# stm32pcb.net
KiCad netlist of a schematic drawn in Altium Designer
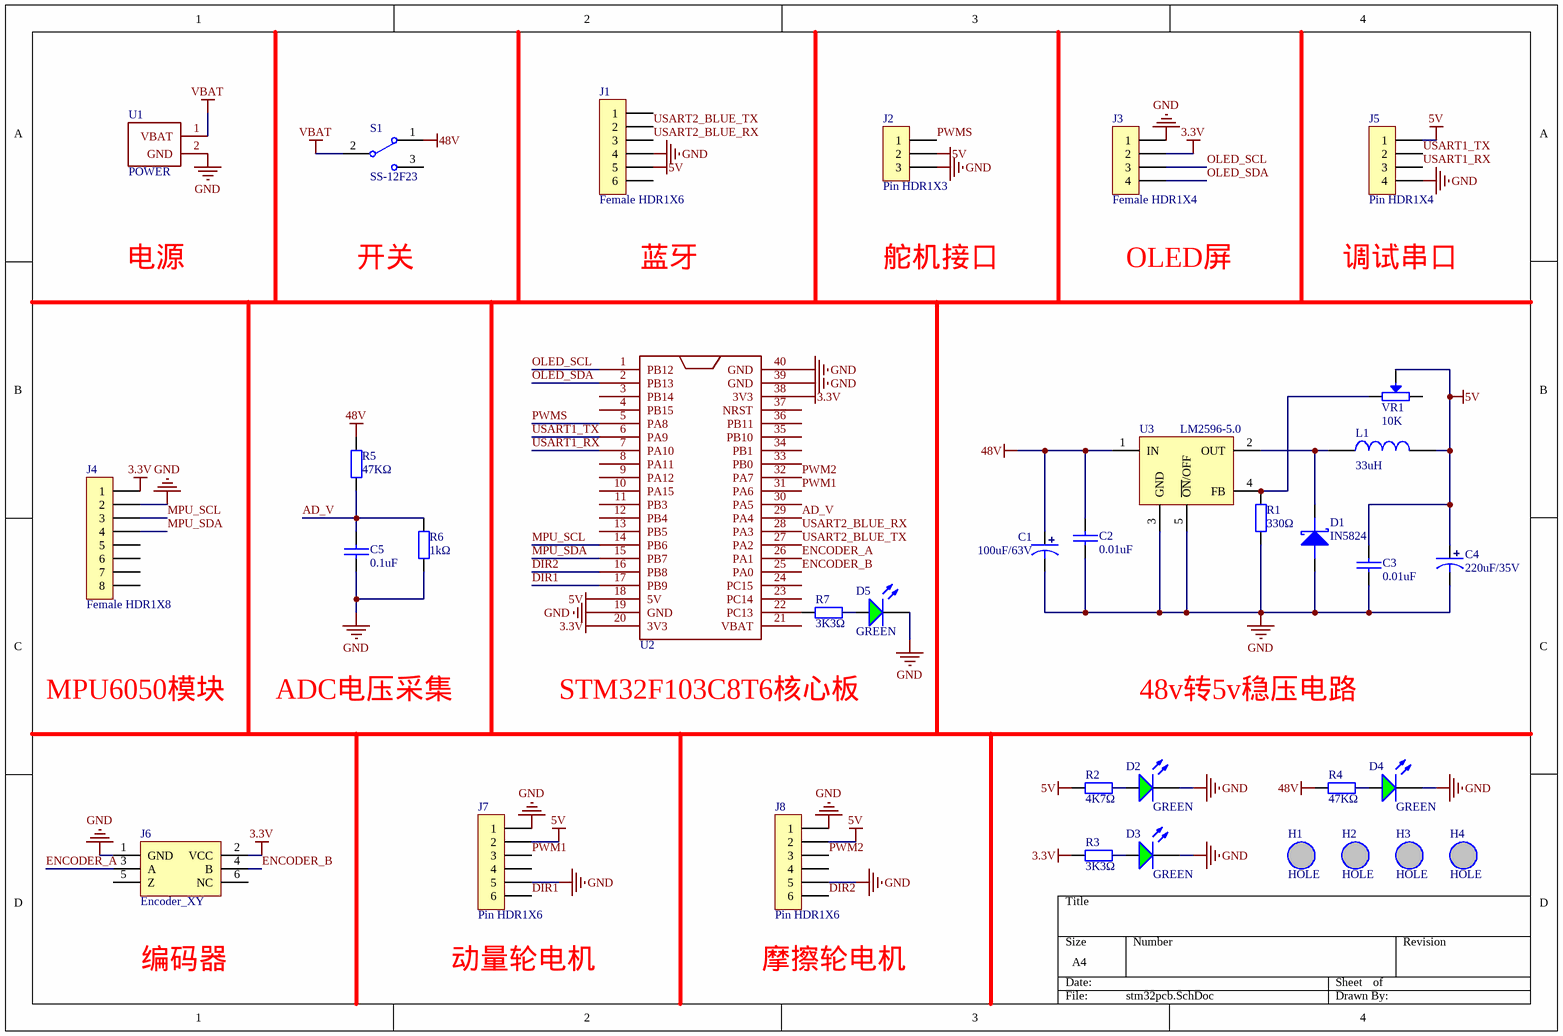
[diagram p0: stm32pcb.SchDoc]

(export (version "E")
  (design (tool "Eeschema 10.0.6"))
  (components
    (comp (ref "C1")
      (value "100uF/63V")
      (footprint "SMD-EC8X8X10")
      (description "贴片电解电容")
      (libsource (lib "self_schlib v1.8.6") (part "SMD_ECAP"))
    )
    (comp (ref "C2")
      (value "0.01uF")
      (footprint "0603C")
      (description "无极性电容")
      (libsource (lib "self_schlib v1.8.6") (part "CAP_1"))
    )
    (comp (ref "C3")
      (value "0.01uF")
      (footprint "0603C")
      (description "无极性电容")
      (libsource (lib "self_schlib v1.8.6") (part "CAP_1"))
    )
    (comp (ref "C4")
      (value "220uF/35V")
      (footprint "SMD-EC8X8X10")
      (description "贴片电解电容")
      (libsource (lib "self_schlib v1.8.6") (part "SMD_ECAP"))
    )
    (comp (ref "C5")
      (value "0.1uF")
      (footprint "0603C")
      (description "无极性电容")
      (libsource (lib "self_schlib v1.8.6") (part "CAP_1"))
    )
    (comp (ref "D1")
      (value "IN5824")
      (footprint "SMA/DO-214AC")
      (description "肖特基二极管")
      (libsource (lib "二极管") (part "DIODE SCHOTTKY"))
    )
    (comp (ref "D2")
      (value "GREEN")
      (footprint "0805_LED_S1")
      (description "发光二极管")
      (libsource (lib "Miscellaneous Devices Legend") (part "0805 翠绿"))
    )
    (comp (ref "D3")
      (value "GREEN")
      (footprint "0805_LED_S1")
      (description "发光二极管")
      (libsource (lib "Miscellaneous Devices Legend") (part "0805 翠绿"))
    )
    (comp (ref "D4")
      (value "GREEN")
      (footprint "0805_LED_S1")
      (description "发光二极管")
      (libsource (lib "Miscellaneous Devices Legend") (part "0805 翠绿"))
    )
    (comp (ref "D5")
      (value "GREEN")
      (footprint "0805_LED_S1")
      (description "发光二极管")
      (libsource (lib "Miscellaneous Devices Legend") (part "0805 翠绿"))
    )
    (comp (ref "H1")
      (value "HOLE")
      (footprint "LQ_SCROW3&5MM")
      (description "固定孔")
      (libsource (lib "test001") (part "HOLE"))
    )
    (comp (ref "H2")
      (value "HOLE")
      (footprint "LQ_SCROW3&5MM")
      (description "固定孔")
      (libsource (lib "test001") (part "HOLE"))
    )
    (comp (ref "H3")
      (value "HOLE")
      (footprint "LQ_SCROW3&5MM")
      (description "固定孔")
      (libsource (lib "test001") (part "HOLE"))
    )
    (comp (ref "H4")
      (value "HOLE")
      (footprint "LQ_SCROW3&5MM")
      (description "固定孔")
      (libsource (lib "test001") (part "HOLE"))
    )
    (comp (ref "J1")
      (value "Female HDR1X6")
      (footprint "Fe-HDR1X6/2.54-S")
      (libsource (lib "self_schlib v1.8.6") (part "Female HDR1X6"))
    )
    (comp (ref "J2")
      (value "Pin HDR1X3")
      (footprint "Pin HDR1X3/2.54mm-W")
      (libsource (lib "self_schlib v1.8.6") (part "Pin HDR1X3"))
    )
    (comp (ref "J3")
      (value "Female HDR1X4")
      (footprint "Fe-HDR1X4/2.54-S")
      (libsource (lib "self_schlib v1.8.6") (part "Female HDR1X4"))
    )
    (comp (ref "J4")
      (value "Female HDR1X8")
      (footprint "Fe-HDR1X8/2.54-S")
      (libsource (lib "self_schlib v1.8.6") (part "Female HDR1X8"))
    )
    (comp (ref "J5")
      (value "Pin HDR1X4")
      (footprint "Pin HDR1X4/2.54mm-W")
      (libsource (lib "self_schlib v1.8.6") (part "Pin HDR1X4"))
    )
    (comp (ref "J6")
      (value "Encoder_XY")
      (footprint "Pin HDR2X3/2.54mm-S")
      (description "正交编码器")
      (libsource (lib "self_schlib v1.8.6") (part "Encoder_XY"))
    )
    (comp (ref "J7")
      (value "Pin HDR1X6")
      (footprint "Pin HDR1X6/2.54mm-W")
      (libsource (lib "self_schlib v1.8.6") (part "Pin HDR1X6"))
    )
    (comp (ref "J8")
      (value "Pin HDR1X6")
      (footprint "Pin HDR1X6/2.54mm-W")
      (libsource (lib "self_schlib v1.8.6") (part "Pin HDR1X6"))
    )
    (comp (ref "L1")
      (value "33uH")
      (footprint "CD75")
      (description "INDUCTOR")
      (libsource (lib "电感") (part "INDUCTOR"))
    )
    (comp (ref "R1")
      (value "330Ω")
      (footprint "0603_R")
      (description "贴片电阻")
      (libsource (lib "") (part "0603 330Ω (3300) 1%_1"))
    )
    (comp (ref "R2")
      (value "4K7Ω")
      (footprint "0603_R")
      (description "贴片电阻")
      (libsource (lib "Miscellaneous Devices Legend") (part "0603 330Ω (3300) 1%"))
    )
    (comp (ref "R3")
      (value "3K3Ω")
      (footprint "0603_R")
      (description "贴片电阻")
      (libsource (lib "Miscellaneous Devices Legend") (part "0603 330Ω (3300) 1%"))
    )
    (comp (ref "R4")
      (value "47KΩ")
      (footprint "0603_R")
      (description "贴片电阻")
      (libsource (lib "Miscellaneous Devices Legend") (part "0603 330Ω (3300) 1%"))
    )
    (comp (ref "R5")
      (value "47KΩ")
      (footprint "0603_R")
      (description "贴片电阻")
      (libsource (lib "") (part "0603 330Ω (3300) 1%_1"))
    )
    (comp (ref "R6")
      (value "1kΩ")
      (footprint "0603_R")
      (description "贴片电阻")
      (libsource (lib "") (part "0603 330Ω (3300) 1%_1"))
    )
    (comp (ref "R7")
      (value "3K3Ω")
      (footprint "0603_R")
      (description "贴片电阻")
      (libsource (lib "Miscellaneous Devices Legend") (part "0603 330Ω (3300) 1%"))
    )
    (comp (ref "S1")
      (value "SS-12F23")
      (footprint "SS-12F23")
      (libsource (lib "self_schlib v1.8.6") (part "SS-12F23"))
    )
    (comp (ref "U1")
      (value "POWER")
      (footprint "KF301-5.0-2P")
      (libsource (lib "self_schlib v1.8.6") (part "电源焊点"))
    )
    (comp (ref "U2")
      (value "STM32F103C8T6 MODULE")
      (footprint "STM32F103C8T6 MODULE")
      (libsource (lib "self_schlib v1.8.6") (part "STM32F103C8T6 MODULE"))
    )
    (comp (ref "U3")
      (value "LM2596-5.0")
      (footprint "TO263-5A")
      (description "DC降压芯片")
      (libsource (lib "self_schlib v1.8.6") (part "LM2596-5.0"))
    )
    (comp (ref "VR1") (value "10K") (footprint "3296W") (libsource (lib "self_schlib v1.8.6") (part "RESVR")))
  )
  (nets
    (net (code "1") (name "/AD_V") (class "Default")
      (node (ref "C5") (pin "2") (pinfunction "2_2") (pintype "passive"))
      (node (ref "R5") (pin "2") (pinfunction "2_2") (pintype "passive"))
      (node (ref "R6") (pin "1") (pinfunction "1_1") (pintype "passive"))
      (node (ref "U2") (pin "29") (pinfunction "PA4_29") (pintype "passive"))
    )
    (net (code "2") (name "/DIR1") (class "Default")
      (node (ref "J7") (pin "6") (pinfunction "6_6") (pintype "passive"))
      (node (ref "U2") (pin "17") (pinfunction "PB9_17") (pintype "passive"))
    )
    (net (code "3") (name "/DIR2") (class "Default")
      (node (ref "J8") (pin "6") (pinfunction "6_6") (pintype "passive"))
      (node (ref "U2") (pin "16") (pinfunction "PB8_16") (pintype "passive"))
    )
    (net (code "4") (name "/ENCODER_A") (class "Default")
      (node (ref "J6") (pin "3") (pinfunction "A_3") (pintype "passive"))
      (node (ref "U2") (pin "26") (pinfunction "PA1_26") (pintype "passive"))
    )
    (net (code "5") (name "/ENCODER_B") (class "Default")
      (node (ref "J6") (pin "4") (pinfunction "B_4") (pintype "passive"))
      (node (ref "U2") (pin "25") (pinfunction "PA0_25") (pintype "passive"))
    )
    (net (code "6") (name "/MPU_SCL") (class "Default")
      (node (ref "J4") (pin "3") (pinfunction "3_3") (pintype "passive"))
      (node (ref "U2") (pin "14") (pinfunction "PB6_14") (pintype "passive"))
    )
    (net (code "7") (name "/MPU_SDA") (class "Default")
      (node (ref "J4") (pin "4") (pinfunction "4_4") (pintype "passive"))
      (node (ref "U2") (pin "15") (pinfunction "PB7_15") (pintype "passive"))
    )
    (net (code "8") (name "/OLED_SCL") (class "Default")
      (node (ref "J3") (pin "3") (pinfunction "3_3") (pintype "passive"))
      (node (ref "U2") (pin "1") (pinfunction "PB12_1") (pintype "passive"))
    )
    (net (code "9") (name "/OLED_SDA") (class "Default")
      (node (ref "J3") (pin "4") (pinfunction "4_4") (pintype "passive"))
      (node (ref "U2") (pin "2") (pinfunction "PB13_2") (pintype "passive"))
    )
    (net (code "10") (name "/PWM1") (class "Default")
      (node (ref "J7") (pin "3") (pinfunction "3_3") (pintype "passive"))
      (node (ref "U2") (pin "31") (pinfunction "PA6_31") (pintype "passive"))
    )
    (net (code "11") (name "/PWM2") (class "Default")
      (node (ref "J8") (pin "3") (pinfunction "3_3") (pintype "passive"))
      (node (ref "U2") (pin "32") (pinfunction "PA7_32") (pintype "passive"))
    )
    (net (code "12") (name "/PWMS") (class "Default")
      (node (ref "J2") (pin "1") (pinfunction "1_1") (pintype "passive"))
      (node (ref "U2") (pin "5") (pinfunction "PA8_5") (pintype "passive"))
    )
    (net (code "13") (name "/USART1_RX") (class "Default")
      (node (ref "J5") (pin "3") (pinfunction "3_3") (pintype "passive"))
      (node (ref "U2") (pin "7") (pinfunction "PA10_7") (pintype "passive"))
    )
    (net (code "14") (name "/USART1_TX") (class "Default")
      (node (ref "J5") (pin "2") (pinfunction "2_2") (pintype "passive"))
      (node (ref "U2") (pin "6") (pinfunction "PA9_6") (pintype "passive"))
    )
    (net (code "15") (name "/USART2_BLUE_RX") (class "Default")
      (node (ref "J1") (pin "3") (pinfunction "3_3") (pintype "passive"))
      (node (ref "U2") (pin "28") (pinfunction "PA3_28") (pintype "passive"))
    )
    (net (code "16") (name "/USART2_BLUE_TX") (class "Default")
      (node (ref "J1") (pin "2") (pinfunction "2_2") (pintype "passive"))
      (node (ref "U2") (pin "27") (pinfunction "PA2_27") (pintype "passive"))
    )
    (net (code "17") (name "3.3V") (class "Default")
      (node (ref "J3") (pin "2") (pinfunction "2_2") (pintype "passive"))
      (node (ref "J4") (pin "1") (pinfunction "1_1") (pintype "passive"))
      (node (ref "J6") (pin "2") (pinfunction "VCC_2") (pintype "passive"))
      (node (ref "R3") (pin "1") (pinfunction "1_1") (pintype "passive"))
      (node (ref "U2") (pin "20") (pinfunction "3V3_20") (pintype "passive"))
      (node (ref "U2") (pin "38") (pinfunction "3V3_38") (pintype "passive"))
    )
    (net (code "18") (name "5V") (class "Default")
      (node (ref "C3") (pin "2") (pinfunction "2_2") (pintype "passive"))
      (node (ref "C4") (pin "1") (pinfunction "1_1") (pintype "passive"))
      (node (ref "J1") (pin "5") (pinfunction "5_5") (pintype "passive"))
      (node (ref "J2") (pin "2") (pinfunction "2_2") (pintype "passive"))
      (node (ref "J5") (pin "1") (pinfunction "1_1") (pintype "passive"))
      (node (ref "J7") (pin "2") (pinfunction "2_2") (pintype "passive"))
      (node (ref "J8") (pin "2") (pinfunction "2_2") (pintype "passive"))
      (node (ref "L1") (pin "2") (pinfunction "2_2") (pintype "passive"))
      (node (ref "R2") (pin "1") (pinfunction "1_1") (pintype "passive"))
      (node (ref "U2") (pin "18") (pinfunction "5V_18") (pintype "passive"))
      (node (ref "VR1") (pin "2") (pinfunction "2_2") (pintype "passive"))
    )
    (net (code "19") (name "48V") (class "Default")
      (node (ref "C1") (pin "1") (pinfunction "1_1") (pintype "passive"))
      (node (ref "C2") (pin "2") (pinfunction "2_2") (pintype "passive"))
      (node (ref "R4") (pin "1") (pinfunction "1_1") (pintype "passive"))
      (node (ref "R5") (pin "1") (pinfunction "1_1") (pintype "passive"))
      (node (ref "S1") (pin "1") (pinfunction "1_1") (pintype "passive"))
      (node (ref "U3") (pin "1") (pinfunction "IN_1") (pintype "power_in"))
    )
    (net (code "20") (name "GND") (class "Default")
      (node (ref "C1") (pin "2") (pinfunction "2_2") (pintype "passive"))
      (node (ref "C2") (pin "1") (pinfunction "1_1") (pintype "passive"))
      (node (ref "C3") (pin "1") (pinfunction "1_1") (pintype "passive"))
      (node (ref "C4") (pin "2") (pinfunction "2_2") (pintype "passive"))
      (node (ref "C5") (pin "1") (pinfunction "1_1") (pintype "passive"))
      (node (ref "D1") (pin "A") (pinfunction "A_A") (pintype "passive"))
      (node (ref "D2") (pin "K") (pinfunction "K_K") (pintype "passive"))
      (node (ref "D3") (pin "K") (pinfunction "K_K") (pintype "passive"))
      (node (ref "D4") (pin "K") (pinfunction "K_K") (pintype "passive"))
      (node (ref "D5") (pin "K") (pinfunction "K_K") (pintype "passive"))
      (node (ref "J1") (pin "4") (pinfunction "4_4") (pintype "passive"))
      (node (ref "J2") (pin "3") (pinfunction "3_3") (pintype "passive"))
      (node (ref "J3") (pin "1") (pinfunction "1_1") (pintype "passive"))
      (node (ref "J4") (pin "2") (pinfunction "2_2") (pintype "passive"))
      (node (ref "J5") (pin "4") (pinfunction "4_4") (pintype "passive"))
      (node (ref "J6") (pin "1") (pinfunction "GND_1") (pintype "passive"))
      (node (ref "J7") (pin "1") (pinfunction "1_1") (pintype "passive"))
      (node (ref "J7") (pin "5") (pinfunction "5_5") (pintype "passive"))
      (node (ref "J8") (pin "1") (pinfunction "1_1") (pintype "passive"))
      (node (ref "J8") (pin "5") (pinfunction "5_5") (pintype "passive"))
      (node (ref "R1") (pin "2") (pinfunction "2_2") (pintype "passive"))
      (node (ref "R6") (pin "2") (pinfunction "2_2") (pintype "passive"))
      (node (ref "U1") (pin "2") (pinfunction "GND_2") (pintype "passive"))
      (node (ref "U2") (pin "19") (pinfunction "GND_19") (pintype "passive"))
      (node (ref "U2") (pin "39") (pinfunction "GND_39") (pintype "passive"))
      (node (ref "U2") (pin "40") (pinfunction "GND_40") (pintype "passive"))
      (node (ref "U3") (pin "3") (pinfunction "GND_3") (pintype "power_in"))
      (node (ref "U3") (pin "5") (pinfunction "~{ON}/OFF_5") (pintype "passive"))
    )
    (net (code "21") (name "Net-(D2-PadA)") (class "Default")
      (node (ref "D2") (pin "A") (pinfunction "A_A") (pintype "passive"))
      (node (ref "R2") (pin "2") (pinfunction "2_2") (pintype "passive"))
    )
    (net (code "22") (name "Net-(D3-PadA)") (class "Default")
      (node (ref "D3") (pin "A") (pinfunction "A_A") (pintype "passive"))
      (node (ref "R3") (pin "2") (pinfunction "2_2") (pintype "passive"))
    )
    (net (code "23") (name "Net-(D4-PadA)") (class "Default")
      (node (ref "D4") (pin "A") (pinfunction "A_A") (pintype "passive"))
      (node (ref "R4") (pin "2") (pinfunction "2_2") (pintype "passive"))
    )
    (net (code "24") (name "Net-(D5-PadA)") (class "Default")
      (node (ref "D5") (pin "A") (pinfunction "A_A") (pintype "passive"))
      (node (ref "R7") (pin "2") (pinfunction "2_2") (pintype "passive"))
    )
    (net (code "25") (name "Net-(U2-PC13)") (class "Default")
      (node (ref "R7") (pin "1") (pinfunction "1_1") (pintype "passive"))
      (node (ref "U2") (pin "22") (pinfunction "PC13_22") (pintype "passive"))
    )
    (net (code "26") (name "Net-(U3-FB)") (class "Default")
      (node (ref "R1") (pin "1") (pinfunction "1_1") (pintype "passive"))
      (node (ref "U3") (pin "4") (pinfunction "FB_4") (pintype "passive"))
      (node (ref "VR1") (pin "1") (pinfunction "1_1") (pintype "passive"))
    )
    (net (code "27") (name "Net-(U3-OUT)") (class "Default")
      (node (ref "D1") (pin "K") (pinfunction "K_K") (pintype "passive"))
      (node (ref "L1") (pin "1") (pinfunction "1_1") (pintype "passive"))
      (node (ref "U3") (pin "2") (pinfunction "OUT_2") (pintype "power_in"))
    )
    (net (code "28") (name "VBAT") (class "Default")
      (node (ref "S1") (pin "2") (pinfunction "2_2") (pintype "passive"))
      (node (ref "U1") (pin "1") (pinfunction "VBAT_1") (pintype "passive"))
    )
    (net (code "29") (name "unconnected-(J1-Pad1)") (class "Default")
      (node (ref "J1") (pin "1") (pinfunction "1_1") (pintype "passive"))
    )
    (net (code "30") (name "unconnected-(J1-Pad6)") (class "Default")
      (node (ref "J1") (pin "6") (pinfunction "6_6") (pintype "passive"))
    )
    (net (code "31") (name "unconnected-(J4-Pad5)") (class "Default")
      (node (ref "J4") (pin "5") (pinfunction "5_5") (pintype "passive"))
    )
    (net (code "32") (name "unconnected-(J4-Pad6)") (class "Default")
      (node (ref "J4") (pin "6") (pinfunction "6_6") (pintype "passive"))
    )
    (net (code "33") (name "unconnected-(J4-Pad7)") (class "Default")
      (node (ref "J4") (pin "7") (pinfunction "7_7") (pintype "passive"))
    )
    (net (code "34") (name "unconnected-(J4-Pad8)") (class "Default")
      (node (ref "J4") (pin "8") (pinfunction "8_8") (pintype "passive"))
    )
    (net (code "35") (name "unconnected-(J6-NC-Pad6)") (class "Default")
      (node (ref "J6") (pin "6") (pinfunction "NC_6") (pintype "passive"))
    )
    (net (code "36") (name "unconnected-(J6-Z-Pad5)") (class "Default")
      (node (ref "J6") (pin "5") (pinfunction "Z_5") (pintype "passive"))
    )
    (net (code "37") (name "unconnected-(J7-Pad4)") (class "Default")
      (node (ref "J7") (pin "4") (pinfunction "4_4") (pintype "passive"))
    )
    (net (code "38") (name "unconnected-(J8-Pad4)") (class "Default")
      (node (ref "J8") (pin "4") (pinfunction "4_4") (pintype "passive"))
    )
    (net (code "39") (name "unconnected-(S1-Pad3)") (class "Default")
      (node (ref "S1") (pin "3") (pinfunction "3_3") (pintype "passive"))
    )
    (net (code "40") (name "unconnected-(U2-NRST-Pad37)") (class "Default")
      (node (ref "U2") (pin "37") (pinfunction "NRST_37") (pintype "passive"))
    )
    (net (code "41") (name "unconnected-(U2-PA5-Pad30)") (class "Default")
      (node (ref "U2") (pin "30") (pinfunction "PA5_30") (pintype "passive"))
    )
    (net (code "42") (name "unconnected-(U2-PA11-Pad8)") (class "Default")
      (node (ref "U2") (pin "8") (pinfunction "PA11_8") (pintype "passive"))
    )
    (net (code "43") (name "unconnected-(U2-PA12-Pad9)") (class "Default")
      (node (ref "U2") (pin "9") (pinfunction "PA12_9") (pintype "passive"))
    )
    (net (code "44") (name "unconnected-(U2-PA15-Pad10)") (class "Default")
      (node (ref "U2") (pin "10") (pinfunction "PA15_10") (pintype "passive"))
    )
    (net (code "45") (name "unconnected-(U2-PB0-Pad33)") (class "Default")
      (node (ref "U2") (pin "33") (pinfunction "PB0_33") (pintype "passive"))
    )
    (net (code "46") (name "unconnected-(U2-PB1-Pad34)") (class "Default")
      (node (ref "U2") (pin "34") (pinfunction "PB1_34") (pintype "passive"))
    )
    (net (code "47") (name "unconnected-(U2-PB3-Pad11)") (class "Default")
      (node (ref "U2") (pin "11") (pinfunction "PB3_11") (pintype "passive"))
    )
    (net (code "48") (name "unconnected-(U2-PB4-Pad12)") (class "Default")
      (node (ref "U2") (pin "12") (pinfunction "PB4_12") (pintype "passive"))
    )
    (net (code "49") (name "unconnected-(U2-PB5-Pad13)") (class "Default")
      (node (ref "U2") (pin "13") (pinfunction "PB5_13") (pintype "passive"))
    )
    (net (code "50") (name "unconnected-(U2-PB10-Pad35)") (class "Default")
      (node (ref "U2") (pin "35") (pinfunction "PB10_35") (pintype "passive"))
    )
    (net (code "51") (name "unconnected-(U2-PB11-Pad36)") (class "Default")
      (node (ref "U2") (pin "36") (pinfunction "PB11_36") (pintype "passive"))
    )
    (net (code "52") (name "unconnected-(U2-PB14-Pad3)") (class "Default")
      (node (ref "U2") (pin "3") (pinfunction "PB14_3") (pintype "passive"))
    )
    (net (code "53") (name "unconnected-(U2-PB15-Pad4)") (class "Default")
      (node (ref "U2") (pin "4") (pinfunction "PB15_4") (pintype "passive"))
    )
    (net (code "54") (name "unconnected-(U2-PC14-Pad23)") (class "Default")
      (node (ref "U2") (pin "23") (pinfunction "PC14_23") (pintype "passive"))
    )
    (net (code "55") (name "unconnected-(U2-PC15-Pad24)") (class "Default")
      (node (ref "U2") (pin "24") (pinfunction "PC15_24") (pintype "passive"))
    )
    (net (code "56") (name "unconnected-(U2-VBAT-Pad21)") (class "Default")
      (node (ref "U2") (pin "21") (pinfunction "VBAT_21") (pintype "passive"))
    )
    (net (code "57") (name "unconnected-(VR1-Pad2)") (class "Default")
      (node (ref "VR1") (pin "2") (pinfunction "2_2") (pintype "passive"))
    )
  )
)
